# SCH_CadMacroBoard_2024-11-26.net
KiCad netlist of a schematic drawn in EasyEDA
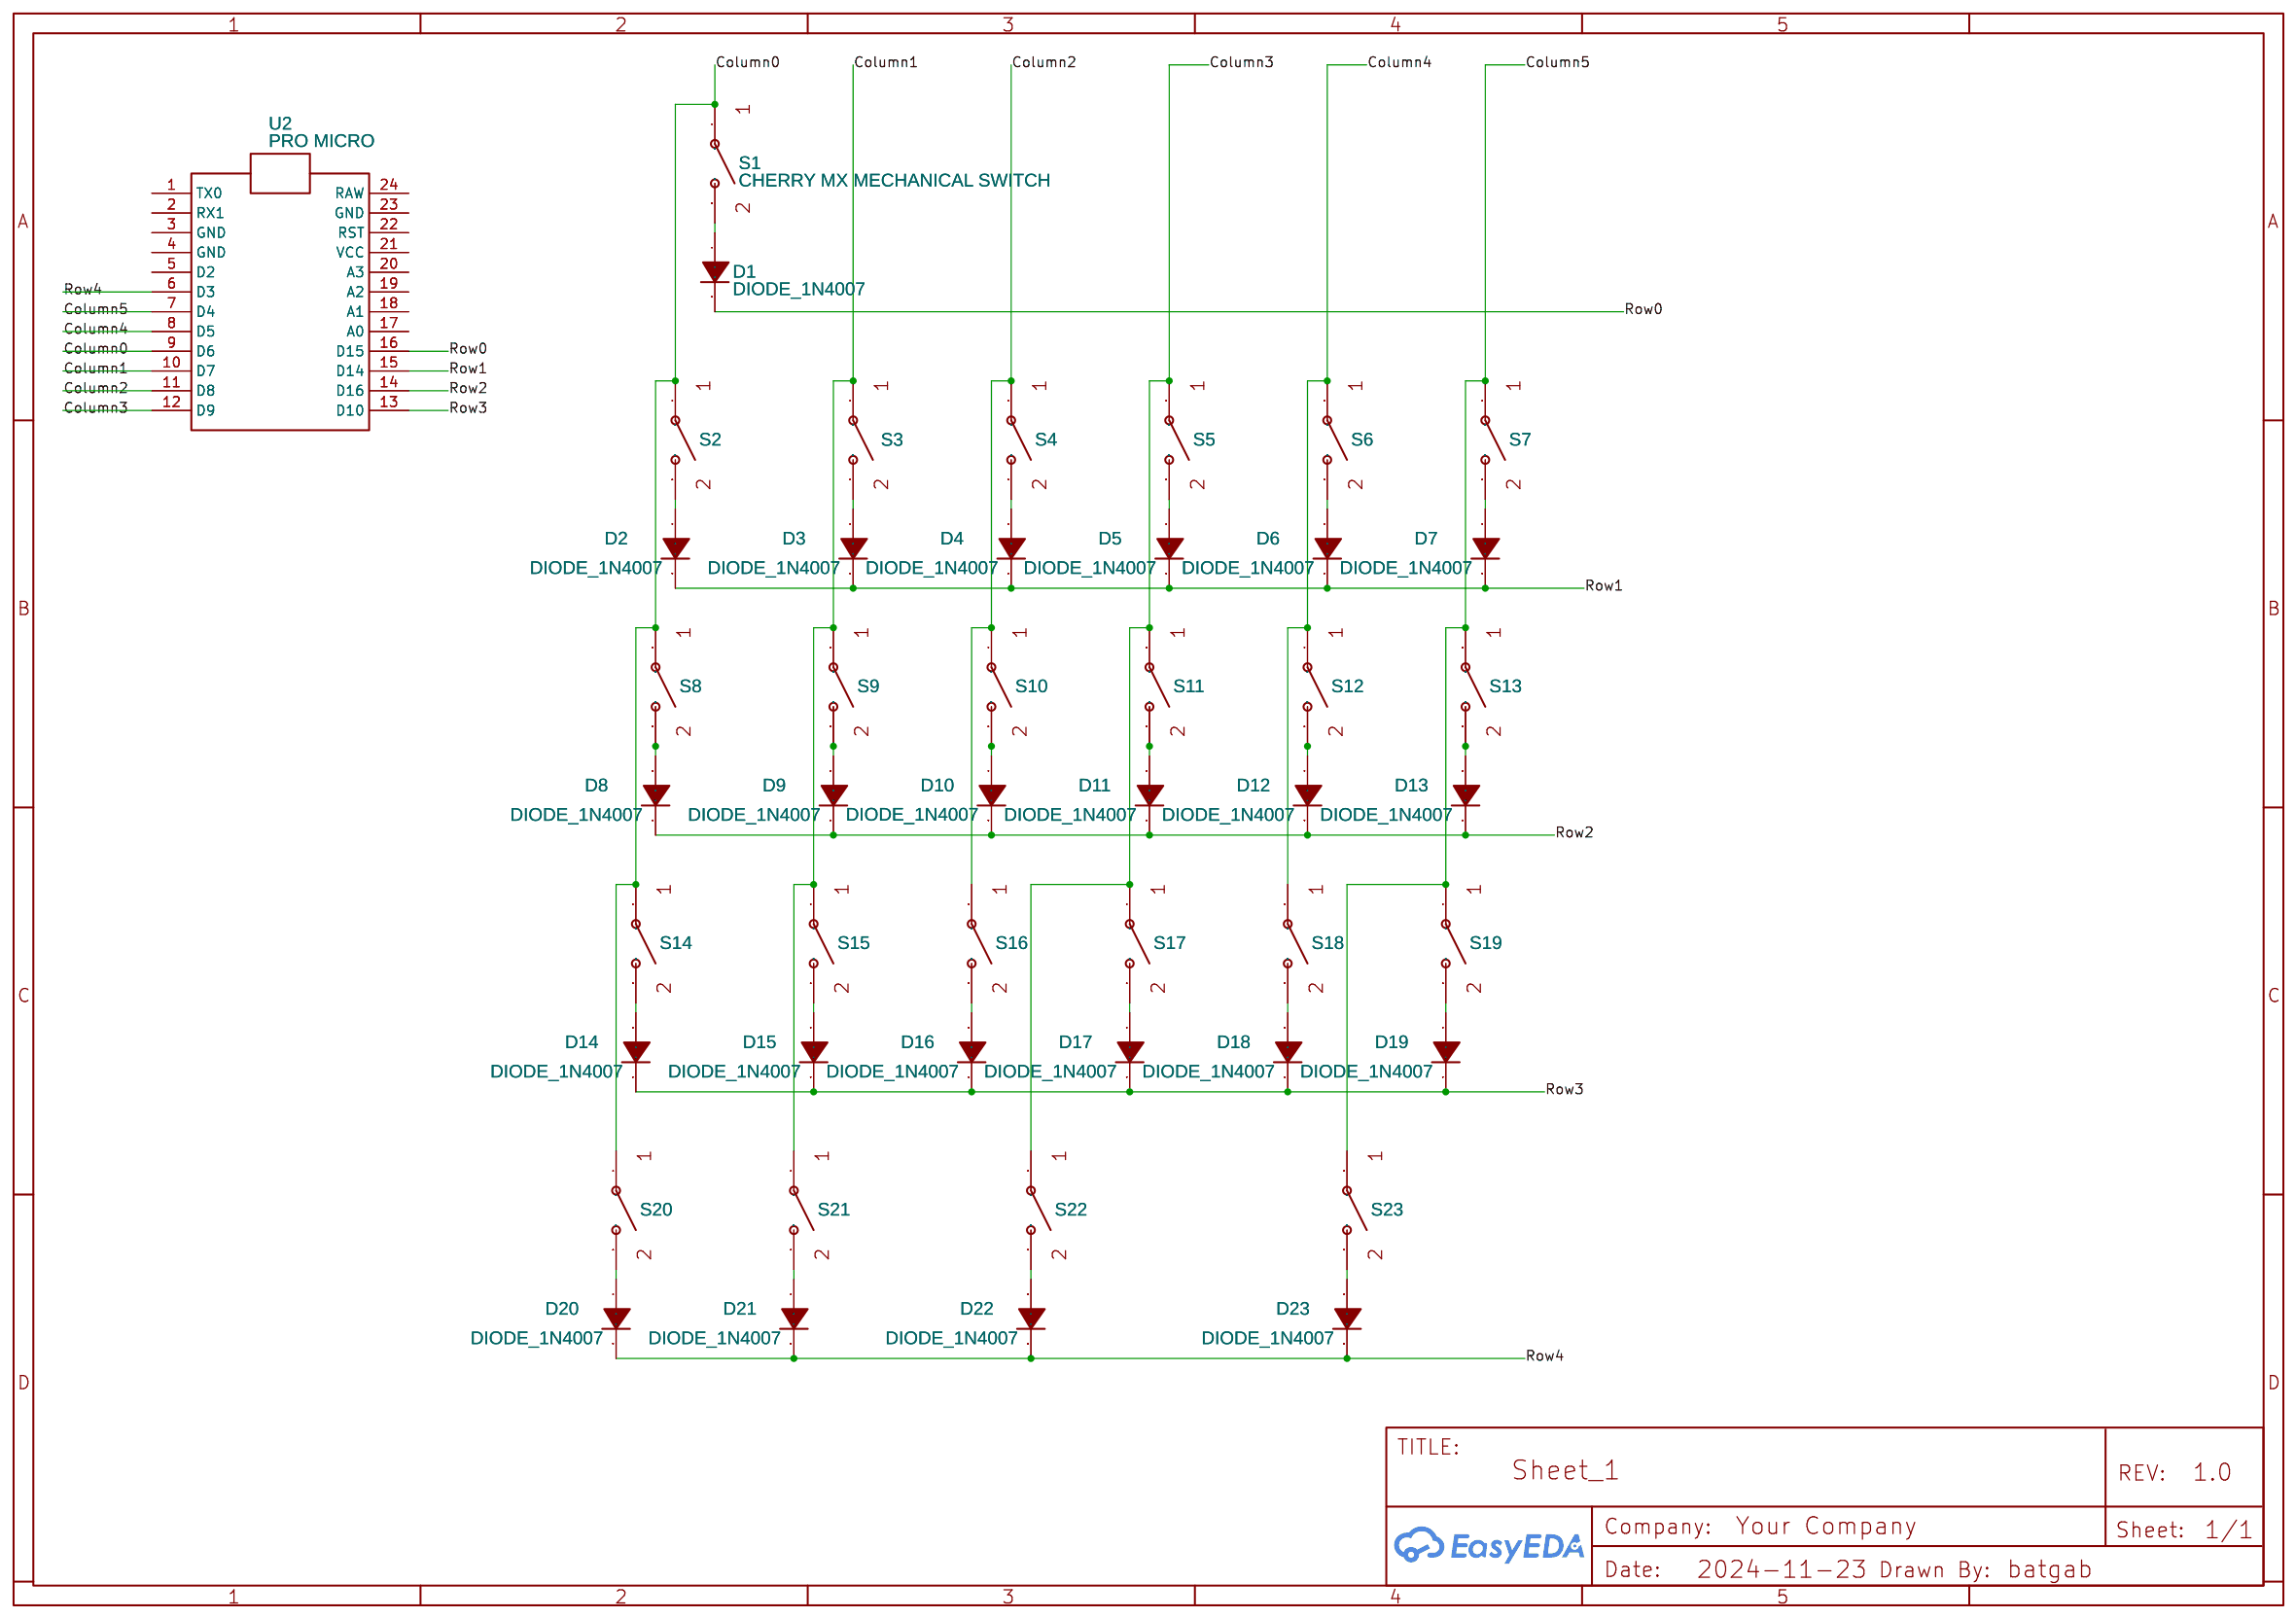
[diagram p0: schematic sheet]

(export (version "E")
  (design (tool "Eeschema 10.0.6"))
  (components
    (comp (ref "D1")
      (value "DIODE_1N4007")
      (fields (field (name "Manufacturer Part") "1N4007") (field (name "Manufacturer") "ST(先科)"))
      (libsource (lib "") (part "1N4007"))
    )
    (comp (ref "D2")
      (value "DIODE_1N4007")
      (fields (field (name "Manufacturer Part") "1N4007") (field (name "Manufacturer") "ST(先科)"))
      (libsource (lib "") (part "1N4007"))
    )
    (comp (ref "D3")
      (value "DIODE_1N4007")
      (fields (field (name "Manufacturer Part") "1N4007") (field (name "Manufacturer") "ST(先科)"))
      (libsource (lib "") (part "1N4007"))
    )
    (comp (ref "D4")
      (value "DIODE_1N4007")
      (fields (field (name "Manufacturer Part") "1N4007") (field (name "Manufacturer") "ST(先科)"))
      (libsource (lib "") (part "1N4007"))
    )
    (comp (ref "D5")
      (value "DIODE_1N4007")
      (fields (field (name "Manufacturer Part") "1N4007") (field (name "Manufacturer") "ST(先科)"))
      (libsource (lib "") (part "1N4007"))
    )
    (comp (ref "D6")
      (value "DIODE_1N4007")
      (fields (field (name "Manufacturer Part") "1N4007") (field (name "Manufacturer") "ST(先科)"))
      (libsource (lib "") (part "1N4007"))
    )
    (comp (ref "D7")
      (value "DIODE_1N4007")
      (fields (field (name "Manufacturer Part") "1N4007") (field (name "Manufacturer") "ST(先科)"))
      (libsource (lib "") (part "1N4007"))
    )
    (comp (ref "D8")
      (value "DIODE_1N4007")
      (fields (field (name "Manufacturer Part") "1N4007") (field (name "Manufacturer") "ST(先科)"))
      (libsource (lib "") (part "1N4007"))
    )
    (comp (ref "D9")
      (value "DIODE_1N4007")
      (fields (field (name "Manufacturer Part") "1N4007") (field (name "Manufacturer") "ST(先科)"))
      (libsource (lib "") (part "1N4007"))
    )
    (comp (ref "D10")
      (value "DIODE_1N4007")
      (fields (field (name "Manufacturer Part") "1N4007") (field (name "Manufacturer") "ST(先科)"))
      (libsource (lib "") (part "1N4007"))
    )
    (comp (ref "D11")
      (value "DIODE_1N4007")
      (fields (field (name "Manufacturer Part") "1N4007") (field (name "Manufacturer") "ST(先科)"))
      (libsource (lib "") (part "1N4007"))
    )
    (comp (ref "D12")
      (value "DIODE_1N4007")
      (fields (field (name "Manufacturer Part") "1N4007") (field (name "Manufacturer") "ST(先科)"))
      (libsource (lib "") (part "1N4007"))
    )
    (comp (ref "D13")
      (value "DIODE_1N4007")
      (fields (field (name "Manufacturer Part") "1N4007") (field (name "Manufacturer") "ST(先科)"))
      (libsource (lib "") (part "1N4007"))
    )
    (comp (ref "D14")
      (value "DIODE_1N4007")
      (fields (field (name "Manufacturer Part") "1N4007") (field (name "Manufacturer") "ST(先科)"))
      (libsource (lib "") (part "1N4007"))
    )
    (comp (ref "D15")
      (value "DIODE_1N4007")
      (fields (field (name "Manufacturer Part") "1N4007") (field (name "Manufacturer") "ST(先科)"))
      (libsource (lib "") (part "1N4007"))
    )
    (comp (ref "D16")
      (value "DIODE_1N4007")
      (fields (field (name "Manufacturer Part") "1N4007") (field (name "Manufacturer") "ST(先科)"))
      (libsource (lib "") (part "1N4007"))
    )
    (comp (ref "D17")
      (value "DIODE_1N4007")
      (fields (field (name "Manufacturer Part") "1N4007") (field (name "Manufacturer") "ST(先科)"))
      (libsource (lib "") (part "1N4007"))
    )
    (comp (ref "D18")
      (value "DIODE_1N4007")
      (fields (field (name "Manufacturer Part") "1N4007") (field (name "Manufacturer") "ST(先科)"))
      (libsource (lib "") (part "1N4007"))
    )
    (comp (ref "D19")
      (value "DIODE_1N4007")
      (fields (field (name "Manufacturer Part") "1N4007") (field (name "Manufacturer") "ST(先科)"))
      (libsource (lib "") (part "1N4007"))
    )
    (comp (ref "D20")
      (value "DIODE_1N4007")
      (fields (field (name "Manufacturer Part") "1N4007") (field (name "Manufacturer") "ST(先科)"))
      (libsource (lib "") (part "1N4007"))
    )
    (comp (ref "D21")
      (value "DIODE_1N4007")
      (fields (field (name "Manufacturer Part") "1N4007") (field (name "Manufacturer") "ST(先科)"))
      (libsource (lib "") (part "1N4007"))
    )
    (comp (ref "D22")
      (value "DIODE_1N4007")
      (fields (field (name "Manufacturer Part") "1N4007") (field (name "Manufacturer") "ST(先科)"))
      (libsource (lib "") (part "1N4007"))
    )
    (comp (ref "D23")
      (value "DIODE_1N4007")
      (fields (field (name "Manufacturer Part") "1N4007") (field (name "Manufacturer") "ST(先科)"))
      (libsource (lib "") (part "1N4007"))
    )
    (comp (ref "S1")
      (value "CHERRY MX MECHANICAL SWITCH")
      (libsource (lib "") (part "CHERRY MX MECHANICAL SWITCH"))
    )
    (comp (ref "S2")
      (value "CHERRY MX MECHANICAL SWITCH")
      (libsource (lib "") (part "CHERRY MX MECHANICAL SWITCH"))
    )
    (comp (ref "S3")
      (value "CHERRY MX MECHANICAL SWITCH")
      (libsource (lib "") (part "CHERRY MX MECHANICAL SWITCH"))
    )
    (comp (ref "S4")
      (value "CHERRY MX MECHANICAL SWITCH")
      (libsource (lib "") (part "CHERRY MX MECHANICAL SWITCH_1"))
    )
    (comp (ref "S5")
      (value "CHERRY MX MECHANICAL SWITCH")
      (libsource (lib "") (part "CHERRY MX MECHANICAL SWITCH_1"))
    )
    (comp (ref "S6")
      (value "CHERRY MX MECHANICAL SWITCH")
      (libsource (lib "") (part "CHERRY MX MECHANICAL SWITCH_1"))
    )
    (comp (ref "S7")
      (value "CHERRY MX MECHANICAL SWITCH")
      (libsource (lib "") (part "CHERRY MX MECHANICAL SWITCH_1"))
    )
    (comp (ref "S8")
      (value "CHERRY MX MECHANICAL SWITCH")
      (libsource (lib "") (part "CHERRY MX MECHANICAL SWITCH"))
    )
    (comp (ref "S9")
      (value "CHERRY MX MECHANICAL SWITCH")
      (libsource (lib "") (part "CHERRY MX MECHANICAL SWITCH"))
    )
    (comp (ref "S10")
      (value "CHERRY MX MECHANICAL SWITCH")
      (libsource (lib "") (part "CHERRY MX MECHANICAL SWITCH_1"))
    )
    (comp (ref "S11")
      (value "CHERRY MX MECHANICAL SWITCH")
      (libsource (lib "") (part "CHERRY MX MECHANICAL SWITCH_1"))
    )
    (comp (ref "S12")
      (value "CHERRY MX MECHANICAL SWITCH")
      (libsource (lib "") (part "CHERRY MX MECHANICAL SWITCH_1"))
    )
    (comp (ref "S13")
      (value "CHERRY MX MECHANICAL SWITCH")
      (libsource (lib "") (part "CHERRY MX MECHANICAL SWITCH_1"))
    )
    (comp (ref "S14")
      (value "CHERRY MX MECHANICAL SWITCH")
      (libsource (lib "") (part "CHERRY MX MECHANICAL SWITCH"))
    )
    (comp (ref "S15")
      (value "CHERRY MX MECHANICAL SWITCH")
      (libsource (lib "") (part "CHERRY MX MECHANICAL SWITCH"))
    )
    (comp (ref "S16")
      (value "CHERRY MX MECHANICAL SWITCH")
      (libsource (lib "") (part "CHERRY MX MECHANICAL SWITCH"))
    )
    (comp (ref "S17")
      (value "CHERRY MX MECHANICAL SWITCH")
      (libsource (lib "") (part "CHERRY MX MECHANICAL SWITCH_1"))
    )
    (comp (ref "S18")
      (value "CHERRY MX MECHANICAL SWITCH")
      (libsource (lib "") (part "CHERRY MX MECHANICAL SWITCH_1"))
    )
    (comp (ref "S19")
      (value "CHERRY MX MECHANICAL SWITCH")
      (libsource (lib "") (part "CHERRY MX MECHANICAL SWITCH_1"))
    )
    (comp (ref "S20")
      (value "CHERRY MX MECHANICAL SWITCH")
      (libsource (lib "") (part "CHERRY MX MECHANICAL SWITCH"))
    )
    (comp (ref "S21")
      (value "CHERRY MX MECHANICAL SWITCH")
      (libsource (lib "") (part "CHERRY MX MECHANICAL SWITCH"))
    )
    (comp (ref "S22")
      (value "CHERRY MX MECHANICAL SWITCH")
      (libsource (lib "") (part "CHERRY MX MECHANICAL SWITCH_1"))
    )
    (comp (ref "S23")
      (value "CHERRY MX MECHANICAL SWITCH")
      (libsource (lib "") (part "CHERRY MX MECHANICAL SWITCH_1"))
    )
    (comp (ref "U2") (value "PRO MICRO") (libsource (lib "") (part "PRO MICRO")))
  )
  (nets
    (net (code "1") (name "/Column0") (class "Default")
      (node (ref "S1") (pin "1") (pinfunction "1_1") (pintype "unspecified"))
      (node (ref "S14") (pin "1") (pinfunction "1_1") (pintype "unspecified"))
      (node (ref "S2") (pin "1") (pinfunction "1_1") (pintype "unspecified"))
      (node (ref "S20") (pin "1") (pinfunction "1_1") (pintype "unspecified"))
      (node (ref "S8") (pin "1") (pinfunction "1_1") (pintype "unspecified"))
      (node (ref "U2") (pin "9") (pinfunction "D6_9") (pintype "unspecified"))
    )
    (net (code "2") (name "/Column1") (class "Default")
      (node (ref "S15") (pin "1") (pinfunction "1_1") (pintype "unspecified"))
      (node (ref "S21") (pin "1") (pinfunction "1_1") (pintype "unspecified"))
      (node (ref "S3") (pin "1") (pinfunction "1_1") (pintype "unspecified"))
      (node (ref "S9") (pin "1") (pinfunction "1_1") (pintype "unspecified"))
      (node (ref "U2") (pin "10") (pinfunction "D7_10") (pintype "unspecified"))
    )
    (net (code "3") (name "/Column2") (class "Default")
      (node (ref "S10") (pin "1") (pinfunction "1_1") (pintype "unspecified"))
      (node (ref "S16") (pin "1") (pinfunction "1_1") (pintype "unspecified"))
      (node (ref "S4") (pin "1") (pinfunction "1_1") (pintype "unspecified"))
      (node (ref "U2") (pin "11") (pinfunction "D8_11") (pintype "unspecified"))
    )
    (net (code "4") (name "/Column3") (class "Default")
      (node (ref "S11") (pin "1") (pinfunction "1_1") (pintype "unspecified"))
      (node (ref "S17") (pin "1") (pinfunction "1_1") (pintype "unspecified"))
      (node (ref "S22") (pin "1") (pinfunction "1_1") (pintype "unspecified"))
      (node (ref "S5") (pin "1") (pinfunction "1_1") (pintype "unspecified"))
      (node (ref "U2") (pin "12") (pinfunction "D9_12") (pintype "unspecified"))
    )
    (net (code "5") (name "/Column4") (class "Default")
      (node (ref "S12") (pin "1") (pinfunction "1_1") (pintype "unspecified"))
      (node (ref "S18") (pin "1") (pinfunction "1_1") (pintype "unspecified"))
      (node (ref "S6") (pin "1") (pinfunction "1_1") (pintype "unspecified"))
      (node (ref "U2") (pin "8") (pinfunction "D5_8") (pintype "unspecified"))
    )
    (net (code "6") (name "/Column5") (class "Default")
      (node (ref "S13") (pin "1") (pinfunction "1_1") (pintype "unspecified"))
      (node (ref "S19") (pin "1") (pinfunction "1_1") (pintype "unspecified"))
      (node (ref "S23") (pin "1") (pinfunction "1_1") (pintype "unspecified"))
      (node (ref "S7") (pin "1") (pinfunction "1_1") (pintype "unspecified"))
      (node (ref "U2") (pin "7") (pinfunction "D4_7") (pintype "unspecified"))
    )
    (net (code "7") (name "/Row0") (class "Default")
      (node (ref "D1") (pin "2") (pinfunction "K_2") (pintype "unspecified"))
      (node (ref "U2") (pin "16") (pinfunction "D15_16") (pintype "unspecified"))
    )
    (net (code "8") (name "/Row1") (class "Default")
      (node (ref "D2") (pin "2") (pinfunction "K_2") (pintype "unspecified"))
      (node (ref "D3") (pin "2") (pinfunction "K_2") (pintype "unspecified"))
      (node (ref "D4") (pin "2") (pinfunction "K_2") (pintype "unspecified"))
      (node (ref "D5") (pin "2") (pinfunction "K_2") (pintype "unspecified"))
      (node (ref "D6") (pin "2") (pinfunction "K_2") (pintype "unspecified"))
      (node (ref "D7") (pin "2") (pinfunction "K_2") (pintype "unspecified"))
      (node (ref "U2") (pin "15") (pinfunction "D14_15") (pintype "unspecified"))
    )
    (net (code "9") (name "/Row2") (class "Default")
      (node (ref "D10") (pin "2") (pinfunction "K_2") (pintype "unspecified"))
      (node (ref "D11") (pin "2") (pinfunction "K_2") (pintype "unspecified"))
      (node (ref "D12") (pin "2") (pinfunction "K_2") (pintype "unspecified"))
      (node (ref "D13") (pin "2") (pinfunction "K_2") (pintype "unspecified"))
      (node (ref "D8") (pin "2") (pinfunction "K_2") (pintype "unspecified"))
      (node (ref "D9") (pin "2") (pinfunction "K_2") (pintype "unspecified"))
      (node (ref "U2") (pin "14") (pinfunction "D16_14") (pintype "unspecified"))
    )
    (net (code "10") (name "/Row3") (class "Default")
      (node (ref "D14") (pin "2") (pinfunction "K_2") (pintype "unspecified"))
      (node (ref "D15") (pin "2") (pinfunction "K_2") (pintype "unspecified"))
      (node (ref "D16") (pin "2") (pinfunction "K_2") (pintype "unspecified"))
      (node (ref "D17") (pin "2") (pinfunction "K_2") (pintype "unspecified"))
      (node (ref "D18") (pin "2") (pinfunction "K_2") (pintype "unspecified"))
      (node (ref "D19") (pin "2") (pinfunction "K_2") (pintype "unspecified"))
      (node (ref "U2") (pin "13") (pinfunction "D10_13") (pintype "unspecified"))
    )
    (net (code "11") (name "/Row4") (class "Default")
      (node (ref "D20") (pin "2") (pinfunction "K_2") (pintype "unspecified"))
      (node (ref "D21") (pin "2") (pinfunction "K_2") (pintype "unspecified"))
      (node (ref "D22") (pin "2") (pinfunction "K_2") (pintype "unspecified"))
      (node (ref "D23") (pin "2") (pinfunction "K_2") (pintype "unspecified"))
      (node (ref "U2") (pin "6") (pinfunction "D3_6") (pintype "unspecified"))
    )
    (net (code "12") (name "Net-(D1-A)") (class "Default")
      (node (ref "D1") (pin "1") (pinfunction "A_1") (pintype "unspecified"))
      (node (ref "S1") (pin "2") (pinfunction "2_2") (pintype "unspecified"))
    )
    (net (code "13") (name "Net-(D2-A)") (class "Default")
      (node (ref "D2") (pin "1") (pinfunction "A_1") (pintype "unspecified"))
      (node (ref "S2") (pin "2") (pinfunction "2_2") (pintype "unspecified"))
    )
    (net (code "14") (name "Net-(D3-A)") (class "Default")
      (node (ref "D3") (pin "1") (pinfunction "A_1") (pintype "unspecified"))
      (node (ref "S3") (pin "2") (pinfunction "2_2") (pintype "unspecified"))
    )
    (net (code "15") (name "Net-(D4-A)") (class "Default")
      (node (ref "D4") (pin "1") (pinfunction "A_1") (pintype "unspecified"))
      (node (ref "S4") (pin "2") (pinfunction "2_2") (pintype "unspecified"))
    )
    (net (code "16") (name "Net-(D5-A)") (class "Default")
      (node (ref "D5") (pin "1") (pinfunction "A_1") (pintype "unspecified"))
      (node (ref "S5") (pin "2") (pinfunction "2_2") (pintype "unspecified"))
    )
    (net (code "17") (name "Net-(D6-A)") (class "Default")
      (node (ref "D6") (pin "1") (pinfunction "A_1") (pintype "unspecified"))
      (node (ref "S6") (pin "2") (pinfunction "2_2") (pintype "unspecified"))
    )
    (net (code "18") (name "Net-(D7-A)") (class "Default")
      (node (ref "D7") (pin "1") (pinfunction "A_1") (pintype "unspecified"))
      (node (ref "S7") (pin "2") (pinfunction "2_2") (pintype "unspecified"))
    )
    (net (code "19") (name "Net-(D8-A)") (class "Default")
      (node (ref "D8") (pin "1") (pinfunction "A_1") (pintype "unspecified"))
      (node (ref "S8") (pin "2") (pinfunction "2_2") (pintype "unspecified"))
    )
    (net (code "20") (name "Net-(D9-A)") (class "Default")
      (node (ref "D9") (pin "1") (pinfunction "A_1") (pintype "unspecified"))
      (node (ref "S9") (pin "2") (pinfunction "2_2") (pintype "unspecified"))
    )
    (net (code "21") (name "Net-(D10-A)") (class "Default")
      (node (ref "D10") (pin "1") (pinfunction "A_1") (pintype "unspecified"))
      (node (ref "S10") (pin "2") (pinfunction "2_2") (pintype "unspecified"))
    )
    (net (code "22") (name "Net-(D11-A)") (class "Default")
      (node (ref "D11") (pin "1") (pinfunction "A_1") (pintype "unspecified"))
      (node (ref "S11") (pin "2") (pinfunction "2_2") (pintype "unspecified"))
    )
    (net (code "23") (name "Net-(D12-A)") (class "Default")
      (node (ref "D12") (pin "1") (pinfunction "A_1") (pintype "unspecified"))
      (node (ref "S12") (pin "2") (pinfunction "2_2") (pintype "unspecified"))
    )
    (net (code "24") (name "Net-(D13-A)") (class "Default")
      (node (ref "D13") (pin "1") (pinfunction "A_1") (pintype "unspecified"))
      (node (ref "S13") (pin "2") (pinfunction "2_2") (pintype "unspecified"))
    )
    (net (code "25") (name "Net-(D14-A)") (class "Default")
      (node (ref "D14") (pin "1") (pinfunction "A_1") (pintype "unspecified"))
      (node (ref "S14") (pin "2") (pinfunction "2_2") (pintype "unspecified"))
    )
    (net (code "26") (name "Net-(D15-A)") (class "Default")
      (node (ref "D15") (pin "1") (pinfunction "A_1") (pintype "unspecified"))
      (node (ref "S15") (pin "2") (pinfunction "2_2") (pintype "unspecified"))
    )
    (net (code "27") (name "Net-(D16-A)") (class "Default")
      (node (ref "D16") (pin "1") (pinfunction "A_1") (pintype "unspecified"))
      (node (ref "S16") (pin "2") (pinfunction "2_2") (pintype "unspecified"))
    )
    (net (code "28") (name "Net-(D17-A)") (class "Default")
      (node (ref "D17") (pin "1") (pinfunction "A_1") (pintype "unspecified"))
      (node (ref "S17") (pin "2") (pinfunction "2_2") (pintype "unspecified"))
    )
    (net (code "29") (name "Net-(D18-A)") (class "Default")
      (node (ref "D18") (pin "1") (pinfunction "A_1") (pintype "unspecified"))
      (node (ref "S18") (pin "2") (pinfunction "2_2") (pintype "unspecified"))
    )
    (net (code "30") (name "Net-(D19-A)") (class "Default")
      (node (ref "D19") (pin "1") (pinfunction "A_1") (pintype "unspecified"))
      (node (ref "S19") (pin "2") (pinfunction "2_2") (pintype "unspecified"))
    )
    (net (code "31") (name "Net-(D20-A)") (class "Default")
      (node (ref "D20") (pin "1") (pinfunction "A_1") (pintype "unspecified"))
      (node (ref "S20") (pin "2") (pinfunction "2_2") (pintype "unspecified"))
    )
    (net (code "32") (name "Net-(D21-A)") (class "Default")
      (node (ref "D21") (pin "1") (pinfunction "A_1") (pintype "unspecified"))
      (node (ref "S21") (pin "2") (pinfunction "2_2") (pintype "unspecified"))
    )
    (net (code "33") (name "Net-(D22-A)") (class "Default")
      (node (ref "D22") (pin "1") (pinfunction "A_1") (pintype "unspecified"))
      (node (ref "S22") (pin "2") (pinfunction "2_2") (pintype "unspecified"))
    )
    (net (code "34") (name "Net-(D23-A)") (class "Default")
      (node (ref "D23") (pin "1") (pinfunction "A_1") (pintype "unspecified"))
      (node (ref "S23") (pin "2") (pinfunction "2_2") (pintype "unspecified"))
    )
    (net (code "35") (name "unconnected-(U2-A0-Pad17)") (class "Default")
      (node (ref "U2") (pin "17") (pinfunction "A0_17") (pintype "unspecified"))
    )
    (net (code "36") (name "unconnected-(U2-A1-Pad18)") (class "Default")
      (node (ref "U2") (pin "18") (pinfunction "A1_18") (pintype "unspecified"))
    )
    (net (code "37") (name "unconnected-(U2-A2-Pad19)") (class "Default")
      (node (ref "U2") (pin "19") (pinfunction "A2_19") (pintype "unspecified"))
    )
    (net (code "38") (name "unconnected-(U2-A3-Pad20)") (class "Default")
      (node (ref "U2") (pin "20") (pinfunction "A3_20") (pintype "unspecified"))
    )
    (net (code "39") (name "unconnected-(U2-D2-Pad5)") (class "Default")
      (node (ref "U2") (pin "5") (pinfunction "D2_5") (pintype "unspecified"))
    )
    (net (code "40") (name "unconnected-(U2-GND-Pad3)") (class "Default")
      (node (ref "U2") (pin "3") (pinfunction "GND_3") (pintype "unspecified"))
    )
    (net (code "41") (name "unconnected-(U2-GND-Pad4)") (class "Default")
      (node (ref "U2") (pin "4") (pinfunction "GND_4") (pintype "unspecified"))
    )
    (net (code "42") (name "unconnected-(U2-GND-Pad23)") (class "Default")
      (node (ref "U2") (pin "23") (pinfunction "GND_23") (pintype "unspecified"))
    )
    (net (code "43") (name "unconnected-(U2-RAW-Pad24)") (class "Default")
      (node (ref "U2") (pin "24") (pinfunction "RAW_24") (pintype "unspecified"))
    )
    (net (code "44") (name "unconnected-(U2-RST-Pad22)") (class "Default")
      (node (ref "U2") (pin "22") (pinfunction "RST_22") (pintype "unspecified"))
    )
    (net (code "45") (name "unconnected-(U2-RX1-Pad2)") (class "Default")
      (node (ref "U2") (pin "2") (pinfunction "RX1_2") (pintype "unspecified"))
    )
    (net (code "46") (name "unconnected-(U2-TX0-Pad1)") (class "Default")
      (node (ref "U2") (pin "1") (pinfunction "TX0_1") (pintype "unspecified"))
    )
    (net (code "47") (name "unconnected-(U2-VCC-Pad21)") (class "Default")
      (node (ref "U2") (pin "21") (pinfunction "VCC_21") (pintype "unspecified"))
    )
  )
)
